# PCA9632_4-Ch_LED_Driver.net
KiCad netlist of a schematic drawn in Altium Designer
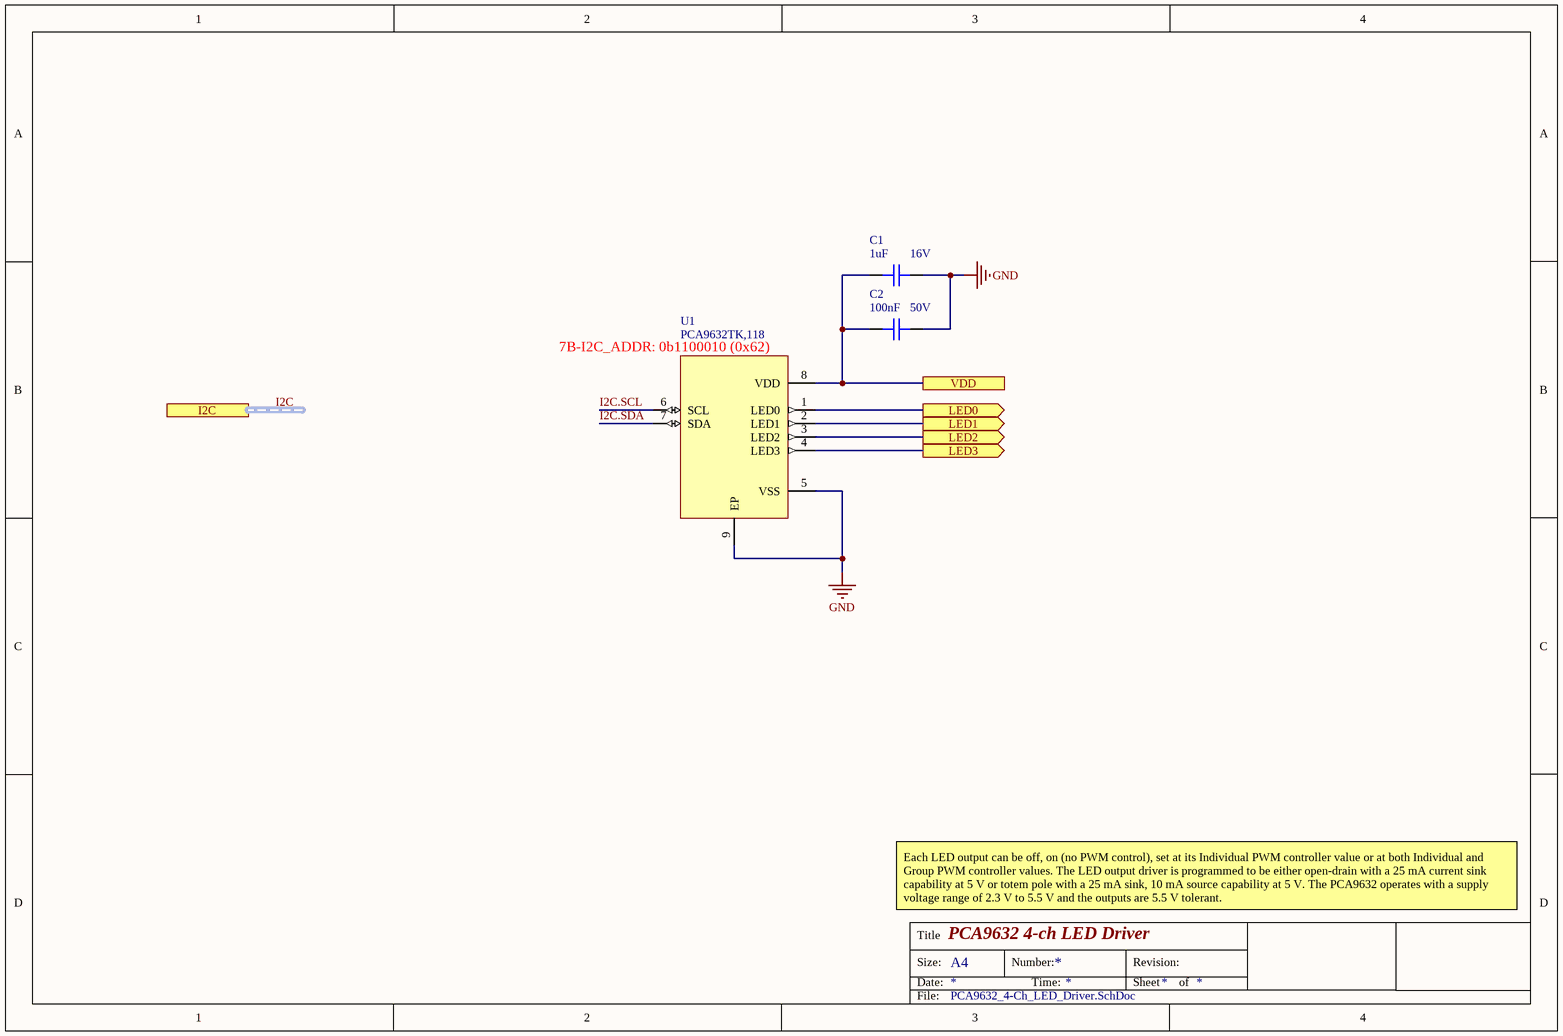
[diagram p0: PCA9632_4-Ch_LED_Driver.SchDoc]

(export (version "E")
  (design (tool "Eeschema 10.0.6"))
  (components
    (comp (ref "C1")
      (value "CAP CER 1UF 16V X5R 0402")
      (footprint "C0402")
      (description "1µF ±10% 16V Ceramic Capacitor X5R 0402 (1005 Metric)")
      (fields
        (field (name "MANUFACTURER") "Yageo")
        (field (name "MANUFACTURER PART NUMBER") "CC0402KRX5R7BB105")
        (field (name "CAPACITANCE") "1uF")
        (field (name "VOLTAGE RATING") "16V")
      )
      (libsource (lib "capacitors_smd") (part "CAP CER 1UF 16V X5R 0402"))
    )
    (comp (ref "C2")
      (value "CAP CER 0.1UF 50V X7R 0402")
      (footprint "C0402")
      (description "0.1µF ±10% 50V Ceramic Capacitor X7R 0402 (1005 Metric)")
      (fields
        (field (name "MANUFACTURER") "TDK")
        (field (name "MANUFACTURER PART NUMBER") "CGA2B3X7R1H104K050BB")
        (field (name "CAPACITANCE") "100nF")
        (field (name "VOLTAGE") "50V")
      )
      (libsource (lib "capacitors_smd") (part "CAP CER 0.1UF 50V X7R 0402"))
    )
    (comp (ref "U1")
      (value "PCA9632TK,118")
      (footprint "SOT908-1")
      (description "LED Driver IC 4 Output Power Switch  PWM Dimming 25mA 8-HVSON (3x3)")
      (fields
        (field (name "MANUFACTURER") "NXP Semiconductors")
        (field (name "7B-I2C_ADDR") "0b1100010 (0x62)")
      )
      (libsource (lib "Control_Board_Model") (part "IC PCA9632TK,118 LED DRVR LIN DIM 25MA 8HVSON"))
    )
  )
  (nets
    (net (code "2") (name "/I2C.SCL") (class "Default")
      (node (ref "U1") (pin "6") (pinfunction "SCL_6") (pintype "bidirectional"))
    )
    (net (code "3") (name "/I2C.SDA") (class "Default")
      (node (ref "U1") (pin "7") (pinfunction "SDA_7") (pintype "bidirectional"))
    )
    (net (code "4") (name "/LED0") (class "Default")
      (node (ref "U1") (pin "1") (pinfunction "LED0_1") (pintype "output"))
    )
    (net (code "5") (name "/LED1") (class "Default")
      (node (ref "U1") (pin "2") (pinfunction "LED1_2") (pintype "output"))
    )
    (net (code "6") (name "/LED2") (class "Default")
      (node (ref "U1") (pin "3") (pinfunction "LED2_3") (pintype "output"))
    )
    (net (code "7") (name "/LED3") (class "Default")
      (node (ref "U1") (pin "4") (pinfunction "LED3_4") (pintype "output"))
    )
    (net (code "8") (name "/VDD") (class "Default")
      (node (ref "C1") (pin "2") (pinfunction "2_2") (pintype "passive"))
      (node (ref "C2") (pin "2") (pinfunction "2_2") (pintype "passive"))
      (node (ref "U1") (pin "8") (pinfunction "VDD_8") (pintype "power_in"))
    )
    (net (code "10") (name "GND") (class "Default")
      (node (ref "C1") (pin "1") (pinfunction "1_1") (pintype "passive"))
      (node (ref "C2") (pin "1") (pinfunction "1_1") (pintype "passive"))
      (node (ref "U1") (pin "5") (pinfunction "VSS_5") (pintype "power_in"))
      (node (ref "U1") (pin "9") (pinfunction "EP_9") (pintype "power_in"))
    )
  )
)
